# design.net
KiCad netlist of a schematic drawn in EasyEDA Pro
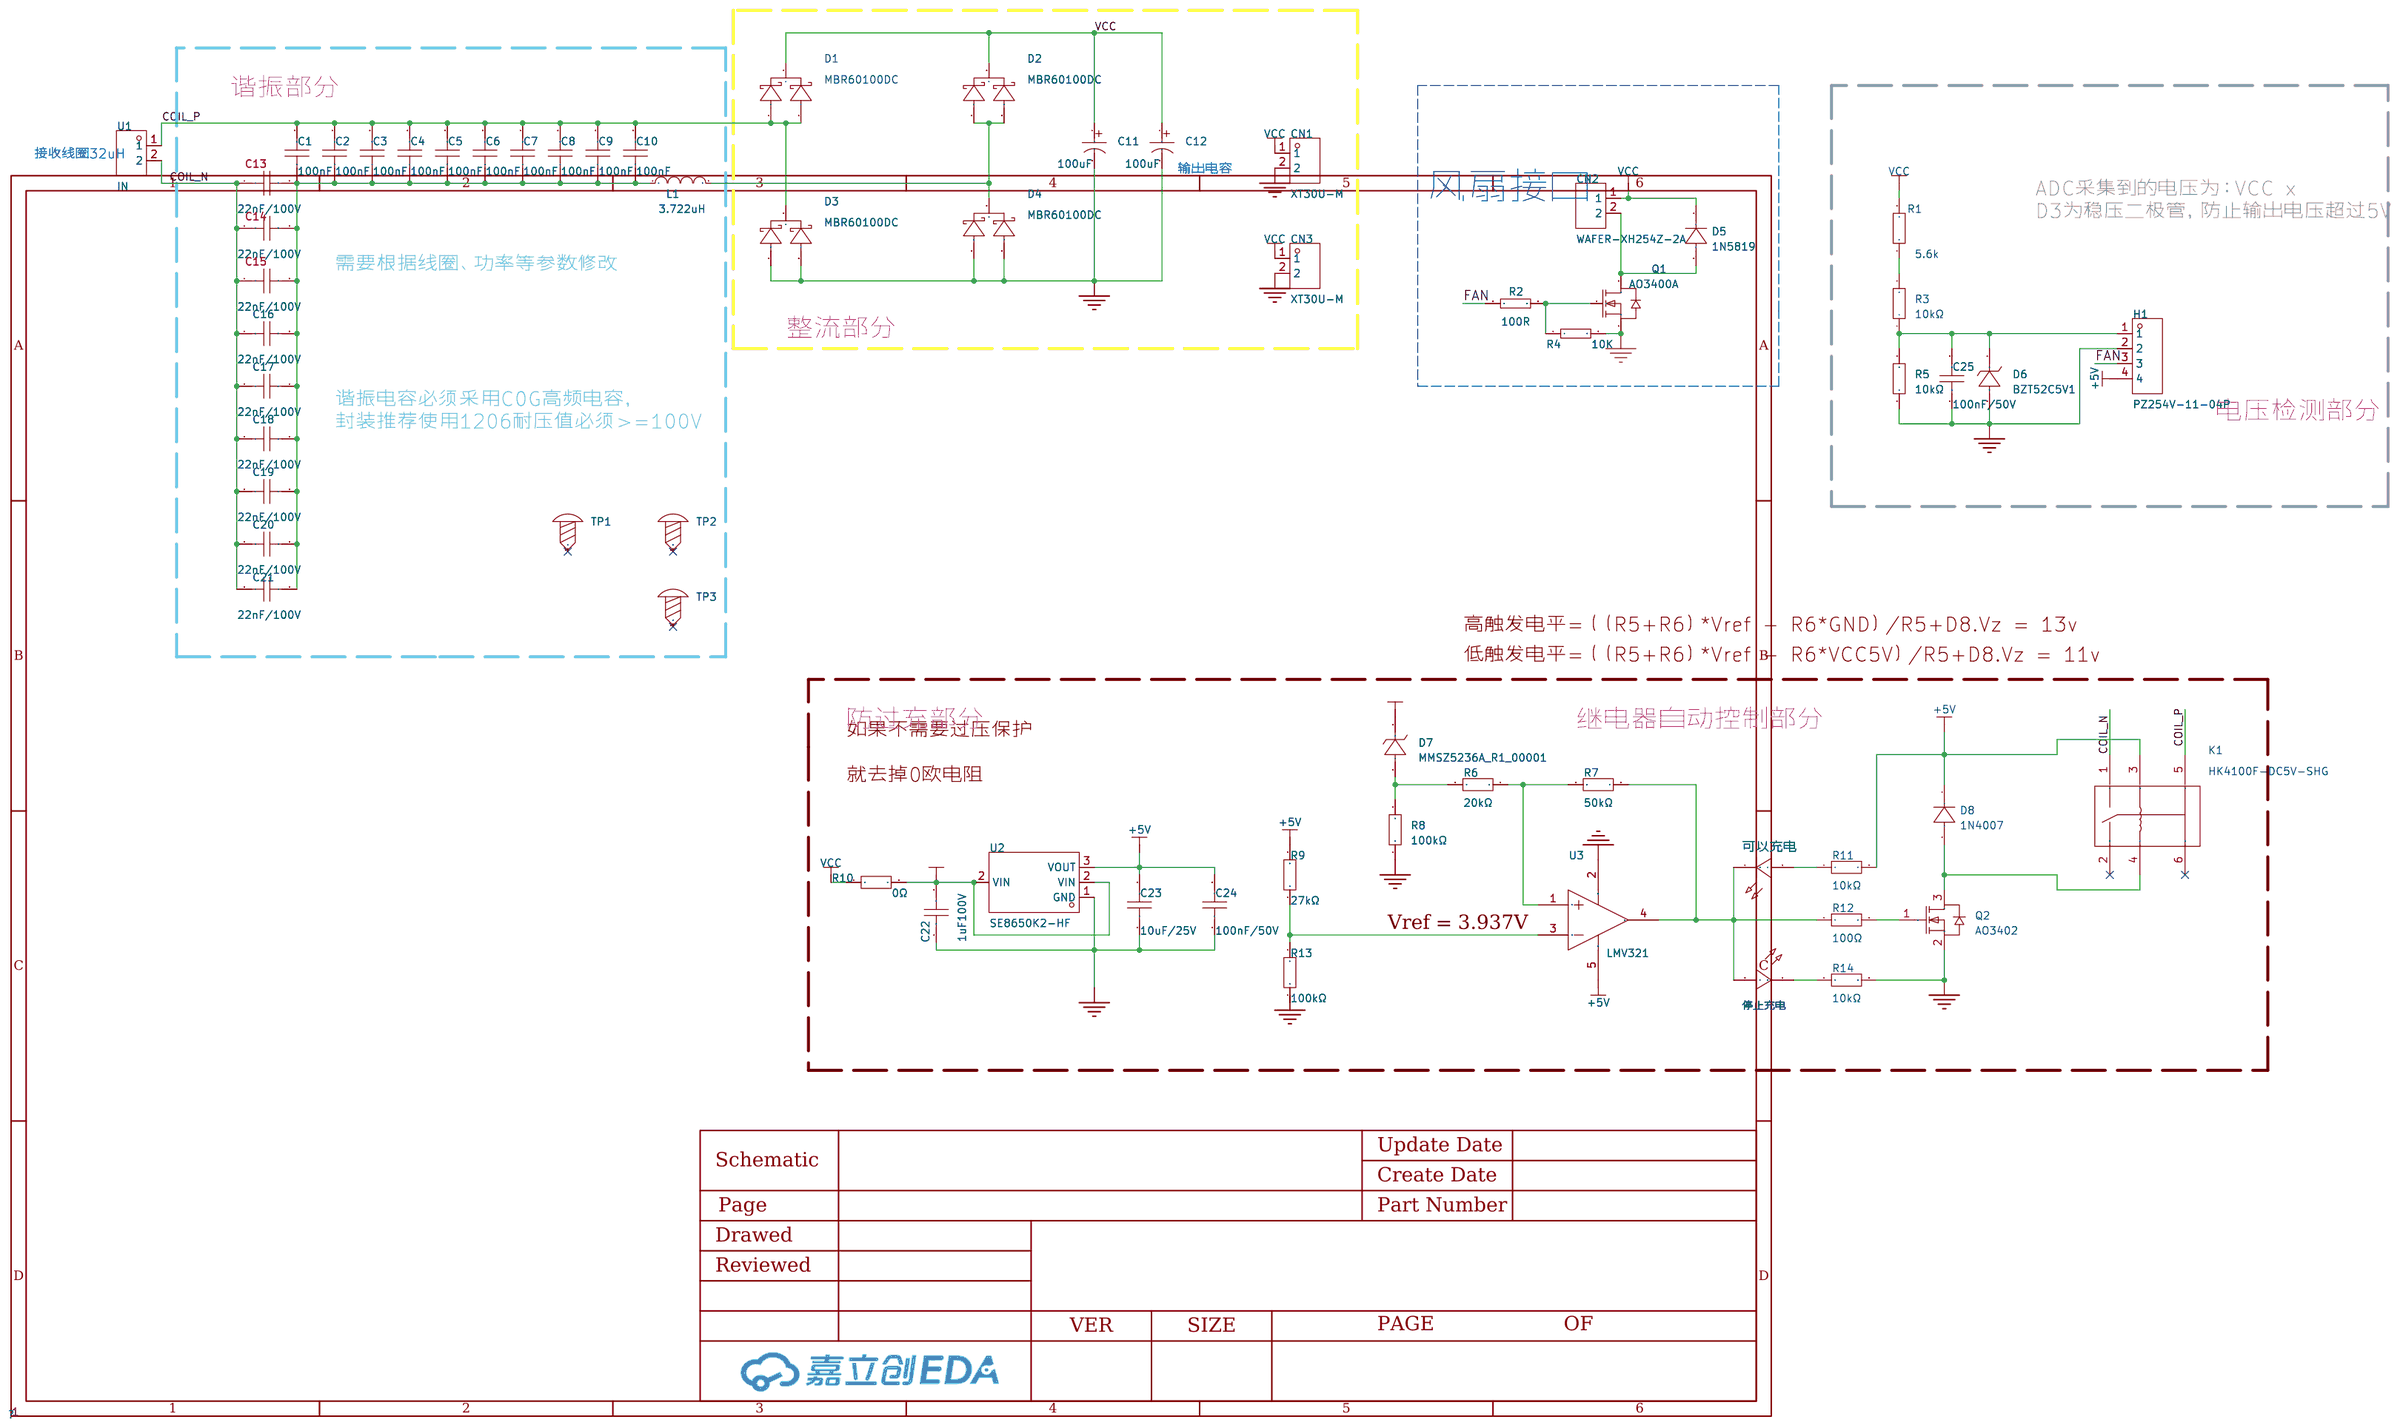
[diagram p0: schematic sheet]

(export (version "E")
  (design (tool "Eeschema 10.0.6"))
  (components
    (comp (ref "C1")
      (value "100nF")
      (footprint "easyedapro:C1206")
      (fields
        (field (name "Manufacturer Part") "GRM31C5C2A104JA01L")
        (field (name "Manufacturer") "muRata(村田)")
      )
      (libsource (lib "easyedapro") (part "CapAcitance"))
    )
    (comp (ref "C2")
      (value "100nF")
      (footprint "easyedapro:C1206")
      (fields
        (field (name "Manufacturer Part") "GRM31C5C2A104JA01L")
        (field (name "Manufacturer") "muRata(村田)")
      )
      (libsource (lib "easyedapro") (part "CapAcitance"))
    )
    (comp (ref "C3")
      (value "100nF")
      (footprint "easyedapro:C1206")
      (fields
        (field (name "Manufacturer Part") "GRM31C5C2A104JA01L")
        (field (name "Manufacturer") "muRata(村田)")
      )
      (libsource (lib "easyedapro") (part "CapAcitance"))
    )
    (comp (ref "C4")
      (value "100nF")
      (footprint "easyedapro:C1206")
      (fields
        (field (name "Manufacturer Part") "GRM31C5C2A104JA01L")
        (field (name "Manufacturer") "muRata(村田)")
      )
      (libsource (lib "easyedapro") (part "CapAcitance"))
    )
    (comp (ref "C5")
      (value "100nF")
      (footprint "easyedapro:C1206")
      (fields
        (field (name "Manufacturer Part") "GRM31C5C2A104JA01L")
        (field (name "Manufacturer") "muRata(村田)")
      )
      (libsource (lib "easyedapro") (part "CapAcitance"))
    )
    (comp (ref "C6")
      (value "100nF")
      (footprint "easyedapro:C1206")
      (fields
        (field (name "Manufacturer Part") "GRM31C5C2A104JA01L")
        (field (name "Manufacturer") "muRata(村田)")
      )
      (libsource (lib "easyedapro") (part "CapAcitance"))
    )
    (comp (ref "C7")
      (value "100nF")
      (footprint "easyedapro:C1206")
      (fields
        (field (name "Manufacturer Part") "GRM31C5C2A104JA01L")
        (field (name "Manufacturer") "muRata(村田)")
      )
      (libsource (lib "easyedapro") (part "CapAcitance"))
    )
    (comp (ref "C8")
      (value "100nF")
      (footprint "easyedapro:C1206")
      (fields
        (field (name "Manufacturer Part") "GRM31C5C2A104JA01L")
        (field (name "Manufacturer") "muRata(村田)")
      )
      (libsource (lib "easyedapro") (part "CapAcitance"))
    )
    (comp (ref "C9")
      (value "100nF")
      (footprint "easyedapro:C1206")
      (fields
        (field (name "Manufacturer Part") "GRM31C5C2A104JA01L")
        (field (name "Manufacturer") "muRata(村田)")
      )
      (libsource (lib "easyedapro") (part "CapAcitance"))
    )
    (comp (ref "C10")
      (value "100nF")
      (footprint "easyedapro:C1206")
      (fields
        (field (name "Manufacturer Part") "GRM31C5C2A104JA01L")
        (field (name "Manufacturer") "muRata(村田)")
      )
      (libsource (lib "easyedapro") (part "CapAcitance"))
    )
    (comp (ref "C11")
      (value "100uF")
      (footprint "easyedapro:CAP-TH_BD10.0-P5.00-D1.0-FD")
      (description "容值:100uF;精度:±20%;额定电压:100V;")
      (fields
        (field (name "Manufacturer Part") "100PX100MEFC10X16")
        (field (name "Manufacturer") "rubycon(红宝石)")
      )
      (libsource (lib "easyedapro") (part "ERS1KM101G16OT"))
    )
    (comp (ref "C12")
      (value "100uF")
      (footprint "easyedapro:CAP-TH_BD10.0-P5.00-D1.0-FD")
      (description "容值:100uF;精度:±20%;额定电压:100V;")
      (fields
        (field (name "Manufacturer Part") "100PX100MEFC10X16")
        (field (name "Manufacturer") "rubycon(红宝石)")
      )
      (libsource (lib "easyedapro") (part "ERS1KM101G16OT"))
    )
    (comp (ref "C13")
      (value "22nF/100V")
      (footprint "easyedapro:C1206")
      (fields
        (field (name "Manufacturer Part") "GRM31C5C2A104JA01L")
        (field (name "Manufacturer") "muRata(村田)")
      )
      (libsource (lib "easyedapro") (part "CapAcitance"))
    )
    (comp (ref "C14")
      (value "22nF/100V")
      (footprint "easyedapro:C1206")
      (fields
        (field (name "Manufacturer Part") "GRM31C5C2A104JA01L")
        (field (name "Manufacturer") "muRata(村田)")
      )
      (libsource (lib "easyedapro") (part "CapAcitance"))
    )
    (comp (ref "C15")
      (value "22nF/100V")
      (footprint "easyedapro:C1206")
      (fields
        (field (name "Manufacturer Part") "GRM31C5C2A104JA01L")
        (field (name "Manufacturer") "muRata(村田)")
      )
      (libsource (lib "easyedapro") (part "CapAcitance"))
    )
    (comp (ref "C16")
      (value "22nF/100V")
      (footprint "easyedapro:C1206")
      (fields
        (field (name "Manufacturer Part") "GRM31C5C2A104JA01L")
        (field (name "Manufacturer") "muRata(村田)")
      )
      (libsource (lib "easyedapro") (part "CapAcitance"))
    )
    (comp (ref "C17")
      (value "22nF/100V")
      (footprint "easyedapro:C1206")
      (fields
        (field (name "Manufacturer Part") "GRM31C5C2A104JA01L")
        (field (name "Manufacturer") "muRata(村田)")
      )
      (libsource (lib "easyedapro") (part "CapAcitance"))
    )
    (comp (ref "C18")
      (value "22nF/100V")
      (footprint "easyedapro:C1206")
      (fields
        (field (name "Manufacturer Part") "GRM31C5C2A104JA01L")
        (field (name "Manufacturer") "muRata(村田)")
      )
      (libsource (lib "easyedapro") (part "CapAcitance"))
    )
    (comp (ref "C19")
      (value "22nF/100V")
      (footprint "easyedapro:C1206")
      (fields
        (field (name "Manufacturer Part") "GRM31C5C2A104JA01L")
        (field (name "Manufacturer") "muRata(村田)")
      )
      (libsource (lib "easyedapro") (part "CapAcitance"))
    )
    (comp (ref "C20")
      (value "22nF/100V")
      (footprint "easyedapro:C1206")
      (fields
        (field (name "Manufacturer Part") "GRM31C5C2A104JA01L")
        (field (name "Manufacturer") "muRata(村田)")
      )
      (libsource (lib "easyedapro") (part "CapAcitance"))
    )
    (comp (ref "C21")
      (value "22nF/100V")
      (footprint "easyedapro:C1206")
      (fields
        (field (name "Manufacturer Part") "GRM31C5C2A104JA01L")
        (field (name "Manufacturer") "muRata(村田)")
      )
      (libsource (lib "easyedapro") (part "CapAcitance"))
    )
    (comp (ref "C22")
      (value "1uF100V")
      (footprint "easyedapro:C1206")
      (fields
        (field (name "Manufacturer Part") "CL31B105KCHNNNE")
        (field (name "Manufacturer") "SAMSUNG(三星)")
      )
      (libsource (lib "easyedapro") (part "CapAcitance"))
    )
    (comp (ref "C23")
      (value "10uF/25V")
      (footprint "easyedapro:C1206")
      (fields
        (field (name "Manufacturer Part") "CL31A106KAHNNNE")
        (field (name "Manufacturer") "SAMSUNG(三星)")
      )
      (libsource (lib "easyedapro") (part "CapAcitance"))
    )
    (comp (ref "C24")
      (value "100nF/50V")
      (footprint "easyedapro:C1206")
      (fields
        (field (name "Manufacturer Part") "CL31B104KBCNNNC")
        (field (name "Manufacturer") "SAMSUNG(三星)")
      )
      (libsource (lib "easyedapro") (part "CapAcitance"))
    )
    (comp (ref "C25")
      (value "100nF/50V")
      (footprint "easyedapro:C1206")
      (fields
        (field (name "Manufacturer Part") "CL31B104KBCNNNC")
        (field (name "Manufacturer") "SAMSUNG(三星)")
      )
      (libsource (lib "easyedapro") (part "CapAcitance"))
    )
    (comp (ref "CN1")
      (value "XT30U-M")
      (footprint "easyedapro:CONN-TH_XT30U-M")
      (description "类别:-;类型1:-;")
      (fields (field (name "Manufacturer") "AMASS(艾迈斯)"))
      (libsource (lib "easyedapro") (part "XT30U-M"))
    )
    (comp (ref "CN2")
      (value "WAFER-XH254Z-2A")
      (footprint "easyedapro:CONN-TH_2P-P2.50_XH-2A_3045048")
      (description "插针结构:1x2P;间距:2.54mm;安装方式:直插;参考系列:XH;总PIN数:2P;排数:1;每排PIN数:2;额定电流:3A;工作温度范围:-25°C~+85°C;")
      (fields (field (name "Manufacturer") "HANBO(汉博)"))
      (libsource (lib "easyedapro") (part "WAFER-XH254Z-2A"))
    )
    (comp (ref "CN3")
      (value "XT30U-M")
      (footprint "easyedapro:CONN-TH_XT30U-M")
      (description "类别:-;类型1:-;")
      (fields (field (name "Manufacturer") "AMASS(艾迈斯)"))
      (libsource (lib "easyedapro") (part "XT30U-M"))
    )
    (comp (ref "D1")
      (value "MBR60100DC")
      (footprint "easyedapro:TO-263-3_L10.2-W9.0-P5.08-LS15.2-BR")
      (description "正向压降(Vf):840mV@30A;直流反向耐压(Vr):100V;整流电流:60A;")
      (fields (field (name "Manufacturer") "YFW(佑风微)"))
      (libsource (lib "easyedapro") (part "MBR60100DC-R"))
    )
    (comp (ref "D2")
      (value "MBR60100DC")
      (footprint "easyedapro:TO-263-3_L10.2-W9.0-P5.08-LS15.2-BR")
      (description "正向压降(Vf):840mV@30A;直流反向耐压(Vr):100V;整流电流:60A;")
      (fields (field (name "Manufacturer") "YFW(佑风微)"))
      (libsource (lib "easyedapro") (part "MBR60100DC-R"))
    )
    (comp (ref "D3")
      (value "MBR60100DC")
      (footprint "easyedapro:TO-263-3_L10.2-W9.0-P5.08-LS15.2-BR")
      (description "正向压降(Vf):840mV@30A;直流反向耐压(Vr):100V;整流电流:60A;")
      (fields (field (name "Manufacturer") "YFW(佑风微)"))
      (libsource (lib "easyedapro") (part "MBR60100DC-R"))
    )
    (comp (ref "D4")
      (value "MBR60100DC")
      (footprint "easyedapro:TO-263-3_L10.2-W9.0-P5.08-LS15.2-BR")
      (description "正向压降(Vf):840mV@30A;直流反向耐压(Vr):100V;整流电流:60A;")
      (fields (field (name "Manufacturer") "YFW(佑风微)"))
      (libsource (lib "easyedapro") (part "MBR60100DC-R"))
    )
    (comp (ref "D5")
      (value "1N5819")
      (footprint "easyedapro:SMA_L4.3-W2.6-LS5.1-RD")
      (libsource (lib "easyedapro") (part "1N5819_C9900008009"))
    )
    (comp (ref "D6")
      (value "BZT52C5V1")
      (footprint "easyedapro:SOD-123_L2.7-W1.6-LS3.7-RD")
      (description "二极管配置:独立式;稳压值(标称值):5.1V;稳压值(范围):4.85V~5.36V;功率(Pd):500mW;")
      (fields (field (name "Manufacturer") "宏迦橙"))
      (libsource (lib "easyedapro") (part "BZT52C5V1_C19077401"))
    )
    (comp (ref "D7")
      (value "MMSZ5236A_R1_00001")
      (footprint "easyedapro:SOD-123F_L2.7-W1.6-LS3.8-RD-1")
      (description "二极管配置:独立式;稳压值(标称值):7.5V;稳压值(范围):7.35V~7.65V;精度:-;功率:500mW;")
      (fields (field (name "Manufacturer") "PANJIT(强茂)"))
      (libsource (lib "easyedapro") (part "MMSZ5236A_R1_00001"))
    )
    (comp (ref "D8")
      (value "1N4007")
      (footprint "easyedapro:SMA_L4.3-W2.5-LS5.0-RD")
      (description "二极管配置:独立式;直流反向耐压(Vr):1kV;平均整流电流(Io):1A;正向压降(Vf):1.1V@1A;反向电流(Ir):5uA@1kV;")
      (fields (field (name "Manufacturer") "TWGMC(台湾迪嘉)"))
      (libsource (lib "easyedapro") (part "1N4007_C727081"))
    )
    (comp (ref "H1")
      (value "PZ254V-11-04P")
      (footprint "easyedapro:HDR-TH_4P-P2.54-V-M")
      (fields (field (name "Manufacturer") "XFCN(兴飞)"))
      (libsource (lib "easyedapro") (part "PZ254V-11-04P_C2691448"))
    )
    (comp (ref "K1")
      (value "HK4100F-DC5V-SHG")
      (footprint "easyedapro:RELAY-TH_HK4100F-DC5V-SHG")
      (description "线圈电压:-;触点形式:-;触点容量(电阻负载):-;最大切换电压:-;最大切换电流:-;")
      (fields (field (name "Manufacturer") "汇科"))
      (libsource (lib "easyedapro") (part "HK4100F-DC5V-SHG"))
    )
    (comp (ref "L1")
      (value "3.722uH")
      (footprint "easyedapro:IND-SMD_L12.5-W12.5_GSDRK127P")
      (description "类型:-;电感值:47uH;精度:±20%;额定电流:-;饱和电流(Isat):3.7A;")
      (fields (field (name "Manufacturer Part") "B82477P4473M000") (field (name "Manufacturer") "TDK"))
      (libsource (lib "easyedapro") (part "B82477P4473M000"))
    )
    (comp (ref "Q1")
      (value "AO3400A")
      (footprint "easyedapro:SOT-23-3_L2.9-W1.3-P1.90-LS2.4-BR")
      (fields (field (name "Manufacturer") "UMW(友台半导体)"))
      (libsource (lib "easyedapro") (part "AO3400A_C347475"))
    )
    (comp (ref "Q2")
      (value "AO3402")
      (footprint "easyedapro:SOT-23-3_L3.0-W1.7-P0.95-LS2.9-BR")
      (fields (field (name "Manufacturer") "PUOLOP(迪浦)"))
      (libsource (lib "easyedapro") (part "AO3402_C351406"))
    )
    (comp (ref "R1")
      (value "5.6k")
      (footprint "easyedapro:R1206")
      (fields
        (field (name "Manufacturer Part") "0805W8F1003T5E")
        (field (name "Manufacturer") "UNI-ROYAL(厚声)")
      )
      (libsource (lib "easyedapro") (part "电阻"))
    )
    (comp (ref "R2") (value "100R") (description "贴片电阻") (libsource (lib "easyedapro") (part "Res-Chip_1")))
    (comp (ref "R3")
      (value "10kΩ")
      (footprint "easyedapro:R1206")
      (fields
        (field (name "Manufacturer Part") "0805W8F1002T5E")
        (field (name "Manufacturer") "UNI-ROYAL(厚声)")
      )
      (libsource (lib "easyedapro") (part "电阻"))
    )
    (comp (ref "R4") (value "10K") (description "贴片电阻") (libsource (lib "easyedapro") (part "Res-Chip")))
    (comp (ref "R5")
      (value "10kΩ")
      (footprint "easyedapro:R1206")
      (fields
        (field (name "Manufacturer Part") "0805W8F1002T5E")
        (field (name "Manufacturer") "UNI-ROYAL(厚声)")
      )
      (libsource (lib "easyedapro") (part "电阻"))
    )
    (comp (ref "R6")
      (value "20kΩ")
      (footprint "easyedapro:R1206")
      (fields
        (field (name "Manufacturer Part") "0805W8F2002T5E")
        (field (name "Manufacturer") "UNI-ROYAL(厚声)")
      )
      (libsource (lib "easyedapro") (part "电阻"))
    )
    (comp (ref "R7")
      (value "50kΩ")
      (footprint "easyedapro:R1206")
      (fields (field (name "Manufacturer Part") "ARG05DTC5002") (field (name "Manufacturer") "Viking(光颉)"))
      (libsource (lib "easyedapro") (part "电阻"))
    )
    (comp (ref "R8")
      (value "100kΩ")
      (footprint "easyedapro:R1206")
      (fields
        (field (name "Manufacturer Part") "0805W8F1003T5E")
        (field (name "Manufacturer") "UNI-ROYAL(厚声)")
      )
      (libsource (lib "easyedapro") (part "电阻"))
    )
    (comp (ref "R9")
      (value "27kΩ")
      (footprint "easyedapro:R1206")
      (fields (field (name "Manufacturer Part") "ERJ6GEYJ273V") (field (name "Manufacturer") "PANASONIC(松下)"))
      (libsource (lib "easyedapro") (part "电阻"))
    )
    (comp (ref "R10")
      (value "0Ω")
      (footprint "easyedapro:R1206")
      (fields
        (field (name "Manufacturer Part") "1206W4J0000T5E")
        (field (name "Manufacturer") "UNI-ROYAL(厚声)")
      )
      (libsource (lib "easyedapro") (part "电阻"))
    )
    (comp (ref "R11")
      (value "10kΩ")
      (footprint "easyedapro:R1206")
      (fields
        (field (name "Manufacturer Part") "0805W8F1002T5E")
        (field (name "Manufacturer") "UNI-ROYAL(厚声)")
      )
      (libsource (lib "easyedapro") (part "电阻"))
    )
    (comp (ref "R12")
      (value "100Ω")
      (footprint "easyedapro:R1206")
      (fields (field (name "Manufacturer Part") "ERJ6RBD1000V") (field (name "Manufacturer") "PANASONIC(松下)"))
      (libsource (lib "easyedapro") (part "电阻"))
    )
    (comp (ref "R13")
      (value "100kΩ")
      (footprint "easyedapro:R1206")
      (fields
        (field (name "Manufacturer Part") "0805W8F1003T5E")
        (field (name "Manufacturer") "UNI-ROYAL(厚声)")
      )
      (libsource (lib "easyedapro") (part "电阻"))
    )
    (comp (ref "R14")
      (value "10kΩ")
      (footprint "easyedapro:R1206")
      (fields
        (field (name "Manufacturer Part") "0805W8F1002T5E")
        (field (name "Manufacturer") "UNI-ROYAL(厚声)")
      )
      (libsource (lib "easyedapro") (part "电阻"))
    )
    (comp (ref "TP1") (value "~") (footprint "easyedapro:M2螺丝") (libsource (lib "easyedapro") (part "螺丝孔")))
    (comp (ref "TP2") (value "~") (footprint "easyedapro:M2螺丝") (libsource (lib "easyedapro") (part "螺丝孔")))
    (comp (ref "TP3") (value "~") (footprint "easyedapro:M2螺丝") (libsource (lib "easyedapro") (part "螺丝孔")))
    (comp (ref "U1")
      (value "IN")
      (footprint "easyedapro:CONN-TH_P5.00_KF301-5.0-2P")
      (fields (field (name "Manufacturer") "KEFA(科发)"))
      (libsource (lib "easyedapro") (part "KF301-5.0-2P"))
    )
    (comp (ref "U2")
      (value "SE8650K2-HF")
      (footprint "easyedapro:SOT-89-3_L4.5-W2.5-P1.50-LS4.2-BR")
      (description "输出类型:固定;输出极性:正;最大输入电压:80V;输出电压:5V;输出电流:-;电源纹波抑制比(PSRR):85dB;")
      (fields (field (name "Manufacturer") "SEAWARD(思旺)"))
      (libsource (lib "easyedapro") (part "SE8650K2-HF"))
    )
    (comp (ref "U3")
      (value "LMV321")
      (footprint "easyedapro:SOT-23-5_L3.0-W1.5-P0.80-LS3.0-BL")
      (description "运放类型:-;放大器组数:-;增益带宽积（GBP）:-;压摆率（SR）:-;电源电压:-;各通道供电电流:-;")
      (fields (field (name "Manufacturer") "IDCHIP(英锐芯)"))
      (libsource (lib "easyedapro") (part "LMV321"))
    )
    (comp (ref "停止充电")
      (value "~")
      (footprint "easyedapro:LED_0805")
      (libsource (lib "easyedapro") (part "LED_G"))
    )
    (comp (ref "可以充电")
      (value "~")
      (footprint "easyedapro:LED_0805")
      (libsource (lib "easyedapro") (part "LED_R"))
    )
  )
  (nets
    (net (code "1") (name "+5V") (class "Default")
      (node (ref "C23") (pin "2") (pinfunction "2_2") (pintype "input"))
      (node (ref "C24") (pin "2") (pinfunction "2_2") (pintype "input"))
      (node (ref "D8") (pin "1") (pinfunction "K_1") (pintype "input"))
      (node (ref "H1") (pin "4") (pinfunction "4_4") (pintype "unspecified"))
      (node (ref "K1") (pin "3") (pinfunction "3_3") (pintype "unspecified"))
      (node (ref "R11") (pin "2") (pinfunction "2_2") (pintype "input"))
      (node (ref "R9") (pin "2") (pinfunction "2_2") (pintype "input"))
      (node (ref "U2") (pin "3") (pinfunction "VOUT_3") (pintype "input"))
      (node (ref "U3") (pin "5") (pinfunction "VCC+_5") (pintype "input"))
    )
    (net (code "2") (name "/COIL_N") (class "Default")
      (node (ref "C13") (pin "1") (pinfunction "1_1") (pintype "input"))
      (node (ref "C14") (pin "1") (pinfunction "1_1") (pintype "input"))
      (node (ref "C15") (pin "1") (pinfunction "1_1") (pintype "input"))
      (node (ref "C16") (pin "1") (pinfunction "1_1") (pintype "input"))
      (node (ref "C17") (pin "1") (pinfunction "1_1") (pintype "input"))
      (node (ref "C18") (pin "1") (pinfunction "1_1") (pintype "input"))
      (node (ref "C19") (pin "1") (pinfunction "1_1") (pintype "input"))
      (node (ref "C20") (pin "1") (pinfunction "1_1") (pintype "input"))
      (node (ref "C21") (pin "1") (pinfunction "1_1") (pintype "input"))
      (node (ref "K1") (pin "1") (pinfunction "1_1") (pintype "unspecified"))
      (node (ref "U1") (pin "2") (pinfunction "2_2") (pintype "input"))
    )
    (net (code "3") (name "/COIL_P") (class "Default")
      (node (ref "C1") (pin "2") (pinfunction "2_2") (pintype "input"))
      (node (ref "C10") (pin "2") (pinfunction "2_2") (pintype "input"))
      (node (ref "C2") (pin "2") (pinfunction "2_2") (pintype "input"))
      (node (ref "C3") (pin "2") (pinfunction "2_2") (pintype "input"))
      (node (ref "C4") (pin "2") (pinfunction "2_2") (pintype "input"))
      (node (ref "C5") (pin "2") (pinfunction "2_2") (pintype "input"))
      (node (ref "C6") (pin "2") (pinfunction "2_2") (pintype "input"))
      (node (ref "C7") (pin "2") (pinfunction "2_2") (pintype "input"))
      (node (ref "C8") (pin "2") (pinfunction "2_2") (pintype "input"))
      (node (ref "C9") (pin "2") (pinfunction "2_2") (pintype "input"))
      (node (ref "D1") (pin "1") (pinfunction "A_1") (pintype "unspecified"))
      (node (ref "D1") (pin "3") (pinfunction "A_3") (pintype "unspecified"))
      (node (ref "D3") (pin "2") (pinfunction "K_2") (pintype "unspecified"))
      (node (ref "K1") (pin "5") (pinfunction "5_5") (pintype "unspecified"))
      (node (ref "U1") (pin "1") (pinfunction "1_1") (pintype "input"))
    )
    (net (code "4") (name "/FAN") (class "Default")
      (node (ref "H1") (pin "3") (pinfunction "3_3") (pintype "unspecified"))
      (node (ref "R2") (pin "1") (pinfunction "1_1") (pintype "unspecified"))
    )
    (net (code "5") (name "GND") (class "Default")
      (node (ref "C11") (pin "2") (pinfunction "2_2") (pintype "input"))
      (node (ref "C12") (pin "2") (pinfunction "2_2") (pintype "input"))
      (node (ref "C22") (pin "1") (pinfunction "1_1") (pintype "input"))
      (node (ref "C23") (pin "1") (pinfunction "1_1") (pintype "input"))
      (node (ref "C24") (pin "1") (pinfunction "1_1") (pintype "input"))
      (node (ref "C25") (pin "1") (pinfunction "1_1") (pintype "input"))
      (node (ref "CN1") (pin "2") (pinfunction "2_2") (pintype "unspecified"))
      (node (ref "CN3") (pin "2") (pinfunction "2_2") (pintype "unspecified"))
      (node (ref "D3") (pin "1") (pinfunction "A_1") (pintype "unspecified"))
      (node (ref "D3") (pin "3") (pinfunction "A_3") (pintype "unspecified"))
      (node (ref "D4") (pin "1") (pinfunction "A_1") (pintype "unspecified"))
      (node (ref "D4") (pin "3") (pinfunction "A_3") (pintype "unspecified"))
      (node (ref "D6") (pin "2") (pinfunction "A_2") (pintype "unspecified"))
      (node (ref "H1") (pin "2") (pinfunction "2_2") (pintype "unspecified"))
      (node (ref "Q1") (pin "2") (pinfunction "S_2") (pintype "unspecified"))
      (node (ref "Q2") (pin "2") (pinfunction "S_2") (pintype "input"))
      (node (ref "R13") (pin "1") (pinfunction "1_1") (pintype "input"))
      (node (ref "R14") (pin "2") (pinfunction "2_2") (pintype "input"))
      (node (ref "R4") (pin "2") (pinfunction "2_2") (pintype "unspecified"))
      (node (ref "R5") (pin "1") (pinfunction "1_1") (pintype "input"))
      (node (ref "R8") (pin "1") (pinfunction "1_1") (pintype "input"))
      (node (ref "U2") (pin "1") (pinfunction "GND_1") (pintype "input"))
      (node (ref "U3") (pin "2") (pinfunction "GND_2") (pintype "input"))
    )
    (net (code "6") (name "Net-(C1-Pad1)") (class "Default")
      (node (ref "C1") (pin "1") (pinfunction "1_1") (pintype "input"))
      (node (ref "C10") (pin "1") (pinfunction "1_1") (pintype "input"))
      (node (ref "C13") (pin "2") (pinfunction "2_2") (pintype "input"))
      (node (ref "C14") (pin "2") (pinfunction "2_2") (pintype "input"))
      (node (ref "C15") (pin "2") (pinfunction "2_2") (pintype "input"))
      (node (ref "C16") (pin "2") (pinfunction "2_2") (pintype "input"))
      (node (ref "C17") (pin "2") (pinfunction "2_2") (pintype "input"))
      (node (ref "C18") (pin "2") (pinfunction "2_2") (pintype "input"))
      (node (ref "C19") (pin "2") (pinfunction "2_2") (pintype "input"))
      (node (ref "C2") (pin "1") (pinfunction "1_1") (pintype "input"))
      (node (ref "C20") (pin "2") (pinfunction "2_2") (pintype "input"))
      (node (ref "C21") (pin "2") (pinfunction "2_2") (pintype "input"))
      (node (ref "C3") (pin "1") (pinfunction "1_1") (pintype "input"))
      (node (ref "C4") (pin "1") (pinfunction "1_1") (pintype "input"))
      (node (ref "C5") (pin "1") (pinfunction "1_1") (pintype "input"))
      (node (ref "C6") (pin "1") (pinfunction "1_1") (pintype "input"))
      (node (ref "C7") (pin "1") (pinfunction "1_1") (pintype "input"))
      (node (ref "C8") (pin "1") (pinfunction "1_1") (pintype "input"))
      (node (ref "C9") (pin "1") (pinfunction "1_1") (pintype "input"))
      (node (ref "L1") (pin "1") (pinfunction "1_1") (pintype "unspecified"))
    )
    (net (code "7") (name "Net-(D4-K)") (class "Default")
      (node (ref "D2") (pin "1") (pinfunction "A_1") (pintype "unspecified"))
      (node (ref "D2") (pin "3") (pinfunction "A_3") (pintype "unspecified"))
      (node (ref "D4") (pin "2") (pinfunction "K_2") (pintype "unspecified"))
      (node (ref "L1") (pin "2") (pinfunction "2_2") (pintype "unspecified"))
    )
    (net (code "8") (name "Net-(D5-A)") (class "Default")
      (node (ref "CN2") (pin "2") (pinfunction "2_2") (pintype "unspecified"))
      (node (ref "D5") (pin "2") (pinfunction "A_2") (pintype "unspecified"))
      (node (ref "Q1") (pin "3") (pinfunction "D_3") (pintype "unspecified"))
    )
    (net (code "9") (name "Net-(D6-K)") (class "Default")
      (node (ref "C25") (pin "2") (pinfunction "2_2") (pintype "input"))
      (node (ref "D6") (pin "1") (pinfunction "K_1") (pintype "unspecified"))
      (node (ref "H1") (pin "1") (pinfunction "1_1") (pintype "unspecified"))
      (node (ref "R3") (pin "1") (pinfunction "1_1") (pintype "input"))
      (node (ref "R5") (pin "2") (pinfunction "2_2") (pintype "input"))
    )
    (net (code "10") (name "Net-(D7-A)") (class "Default")
      (node (ref "D7") (pin "2") (pinfunction "A_2") (pintype "input"))
      (node (ref "R6") (pin "2") (pinfunction "2_2") (pintype "input"))
      (node (ref "R8") (pin "2") (pinfunction "2_2") (pintype "input"))
    )
    (net (code "11") (name "Net-(D8-A)") (class "Default")
      (node (ref "D8") (pin "2") (pinfunction "A_2") (pintype "input"))
      (node (ref "K1") (pin "4") (pinfunction "4_4") (pintype "unspecified"))
      (node (ref "Q2") (pin "3") (pinfunction "D_3") (pintype "input"))
    )
    (net (code "12") (name "Net-(Q1-G)") (class "Default")
      (node (ref "Q1") (pin "1") (pinfunction "G_1") (pintype "unspecified"))
      (node (ref "R2") (pin "2") (pinfunction "2_2") (pintype "unspecified"))
      (node (ref "R4") (pin "1") (pinfunction "1_1") (pintype "unspecified"))
    )
    (net (code "13") (name "Net-(Q2-G)") (class "Default")
      (node (ref "Q2") (pin "1") (pinfunction "G_1") (pintype "input"))
      (node (ref "R12") (pin "2") (pinfunction "2_2") (pintype "input"))
    )
    (net (code "14") (name "Net-(R1-Pad1)") (class "Default")
      (node (ref "R1") (pin "1") (pinfunction "1_1") (pintype "input"))
      (node (ref "R3") (pin "2") (pinfunction "2_2") (pintype "input"))
    )
    (net (code "15") (name "Net-(U3-IN+)") (class "Default")
      (node (ref "R6") (pin "1") (pinfunction "1_1") (pintype "input"))
      (node (ref "R7") (pin "2") (pinfunction "2_2") (pintype "input"))
      (node (ref "U3") (pin "1") (pinfunction "IN+_1") (pintype "input"))
    )
    (net (code "16") (name "Net-(U3-IN-)") (class "Default")
      (node (ref "R13") (pin "2") (pinfunction "2_2") (pintype "input"))
      (node (ref "R9") (pin "1") (pinfunction "1_1") (pintype "input"))
      (node (ref "U3") (pin "3") (pinfunction "IN-_3") (pintype "input"))
    )
    (net (code "17") (name "Net-(U3-OUT)") (class "Default")
      (node (ref "R12") (pin "1") (pinfunction "1_1") (pintype "input"))
      (node (ref "R7") (pin "1") (pinfunction "1_1") (pintype "input"))
      (node (ref "U3") (pin "4") (pinfunction "OUT_4") (pintype "output"))
      (node (ref "停止充电") (pin "2") (pinfunction "A_2") (pintype "input"))
      (node (ref "可以充电") (pin "1") (pinfunction "C_1") (pintype "input"))
    )
    (net (code "18") (name "Net-(停止充电-C)") (class "Default")
      (node (ref "R14") (pin "1") (pinfunction "1_1") (pintype "input"))
      (node (ref "停止充电") (pin "1") (pinfunction "C_1") (pintype "input"))
    )
    (net (code "19") (name "Net-(可以充电-A)") (class "Default")
      (node (ref "R11") (pin "1") (pinfunction "1_1") (pintype "input"))
      (node (ref "可以充电") (pin "2") (pinfunction "A_2") (pintype "input"))
    )
    (net (code "20") (name "VCC") (class "Default")
      (node (ref "C11") (pin "1") (pinfunction "1_1") (pintype "input"))
      (node (ref "C12") (pin "1") (pinfunction "1_1") (pintype "input"))
      (node (ref "CN1") (pin "1") (pinfunction "1_1") (pintype "unspecified"))
      (node (ref "CN2") (pin "1") (pinfunction "1_1") (pintype "unspecified"))
      (node (ref "CN3") (pin "1") (pinfunction "1_1") (pintype "unspecified"))
      (node (ref "D1") (pin "2") (pinfunction "K_2") (pintype "unspecified"))
      (node (ref "D2") (pin "2") (pinfunction "K_2") (pintype "unspecified"))
      (node (ref "D5") (pin "1") (pinfunction "K_1") (pintype "unspecified"))
      (node (ref "R1") (pin "2") (pinfunction "2_2") (pintype "input"))
      (node (ref "R10") (pin "1") (pinfunction "1_1") (pintype "input"))
    )
    (net (code "21") (name "VCCO") (class "Default")
      (node (ref "C22") (pin "2") (pinfunction "2_2") (pintype "input"))
      (node (ref "D7") (pin "1") (pinfunction "K_1") (pintype "input"))
      (node (ref "R10") (pin "2") (pinfunction "2_2") (pintype "input"))
      (node (ref "U2") (pin "2") (pinfunction "VIN_2") (pintype "input"))
    )
    (net (code "22") (name "unconnected-(K1-Pad2)") (class "Default")
      (node (ref "K1") (pin "2") (pinfunction "2_2") (pintype "unspecified+no_connect"))
    )
    (net (code "23") (name "unconnected-(K1-Pad6)") (class "Default")
      (node (ref "K1") (pin "6") (pinfunction "6_6") (pintype "unspecified+no_connect"))
    )
    (net (code "24") (name "unconnected-(TP1-Pad1)") (class "Default")
      (node (ref "TP1") (pin "1") (pinfunction "1_1") (pintype "input+no_connect"))
    )
    (net (code "25") (name "unconnected-(TP2-Pad1)") (class "Default")
      (node (ref "TP2") (pin "1") (pinfunction "1_1") (pintype "input+no_connect"))
    )
    (net (code "26") (name "unconnected-(TP3-Pad1)") (class "Default")
      (node (ref "TP3") (pin "1") (pinfunction "1_1") (pintype "input+no_connect"))
    )
  )
)
